# OPR_Main_v2.net
KiCad netlist of a schematic drawn in EAGLE
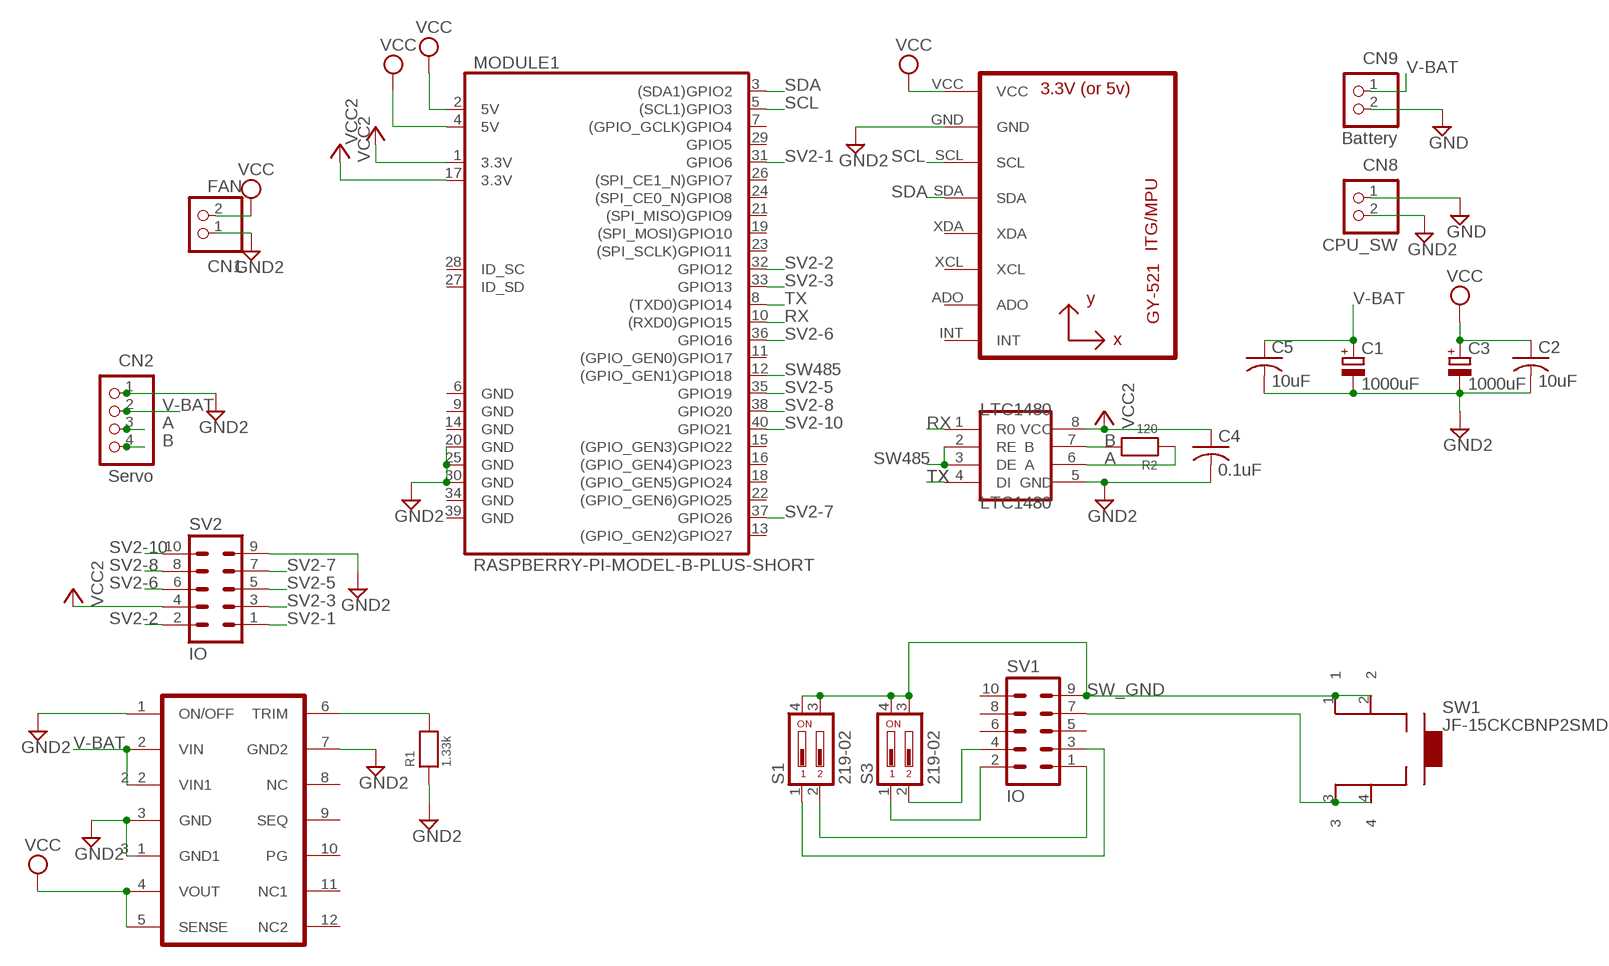
[diagram p0: schematic, sheet 1]

(export (version "E")
  (design (tool "Eeschema 10.0.6"))
  (components
    (comp (ref "C1")
      (value "1000uF")
      (footprint "eagle-import:E5-10,5")
      (libsource (lib "eagle-import") (part "CPOL-EUE5-10.5"))
    )
    (comp (ref "C2")
      (value "10uF")
      (footprint "eagle-import:C3225")
      (libsource (lib "eagle-import") (part "C-USC3225"))
    )
    (comp (ref "C3")
      (value "1000uF")
      (footprint "eagle-import:E5-10,5")
      (libsource (lib "eagle-import") (part "CPOL-EUE5-10.5"))
    )
    (comp (ref "C4")
      (value "0.1uF")
      (footprint "eagle-import:C2012")
      (libsource (lib "eagle-import") (part "rcl_C-USC2012"))
    )
    (comp (ref "C5")
      (value "10uF")
      (footprint "eagle-import:C3225")
      (libsource (lib "eagle-import") (part "C-USC3225"))
    )
    (comp (ref "CN1")
      (value "FAN")
      (footprint "eagle-import:B2B-XH-A")
      (libsource (lib "eagle-import") (part "B2B-XH-A"))
    )
    (comp (ref "CN2")
      (value "Servo")
      (footprint "eagle-import:S4B-XH-A")
      (libsource (lib "eagle-import") (part "S4B-XH-A"))
    )
    (comp (ref "CN8")
      (value "CPU_SW")
      (footprint "eagle-import:B2P-VH")
      (libsource (lib "eagle-import") (part "B2P-VH"))
    )
    (comp (ref "CN9")
      (value "Battery")
      (footprint "eagle-import:B2P-VH")
      (libsource (lib "eagle-import") (part "B2P-VH"))
    )
    (comp (ref "LTC1480")
      (value "LTC1480")
      (footprint "eagle-import:SOIC-8")
      (libsource (lib "eagle-import") (part "LTC1480"))
    )
    (comp (ref "MODULE1")
      (value "RASPBERRY-PI-MODEL-B-PLUS-SHORT")
      (footprint "eagle-import:RASPBERRY-PI-MODEL-B-PLUS-SHORT")
      (libsource (lib "eagle-import") (part "RASPBERRY-PI-MODEL-B-PLUS-SHORT"))
    )
    (comp (ref "R1")
      (value "1.33k")
      (footprint "eagle-import:0805_NOTHERMALS")
      (libsource (lib "eagle-import") (part "RESISTOR0805_NOTHERMALS"))
    )
    (comp (ref "R2")
      (value "120")
      (footprint "eagle-import:0805_NOTHERMALS")
      (libsource (lib "eagle-import") (part "RESISTOR0805_NOTHERMALS"))
    )
    (comp (ref "S1")
      (value "219-02")
      (footprint "eagle-import:CTS-219-02")
      (libsource (lib "eagle-import") (part "219-02"))
    )
    (comp (ref "S3")
      (value "219-02")
      (footprint "eagle-import:CTS-219-02")
      (libsource (lib "eagle-import") (part "219-02"))
    )
    (comp (ref "SV1")
      (value "IO")
      (footprint "eagle-import:ML10")
      (libsource (lib "eagle-import") (part "ML10"))
    )
    (comp (ref "SV2")
      (value "IO")
      (footprint "eagle-import:ML10")
      (libsource (lib "eagle-import") (part "ML10"))
    )
    (comp (ref "SW1")
      (value "JF-15CKCBNP2SMD")
      (footprint "eagle-import:JF-15CKCBNP2-SMD")
      (libsource (lib "eagle-import") (part "JF-15CKCBNP2SMD"))
    )
    (comp (ref "U$3")
      (value "OKL-T/W-12N-C")
      (footprint "eagle-import:OKL_T6_W12")
      (libsource (lib "eagle-import") (part "OKL_T6_W12"))
    )
    (comp (ref "U1")
      (value "GY-521MPU6050")
      (footprint "eagle-import:GY-521")
      (libsource (lib "eagle-import") (part "GY-521MPU6050"))
    )
  )
  (nets
    (net (code "1") (name "/A") (class "Default")
      (node (ref "CN2") (pin "3") (pinfunction "3_3") (pintype "passive"))
      (node (ref "LTC1480") (pin "6") (pinfunction "A_6") (pintype "bidirectional"))
      (node (ref "R2") (pin "1") (pinfunction "1_1") (pintype "passive"))
    )
    (net (code "2") (name "/B") (class "Default")
      (node (ref "CN2") (pin "4") (pinfunction "4_4") (pintype "passive"))
      (node (ref "LTC1480") (pin "7") (pinfunction "B_7") (pintype "passive"))
      (node (ref "R2") (pin "2") (pinfunction "2_2") (pintype "passive"))
    )
    (net (code "3") (name "/RX") (class "Default")
      (node (ref "LTC1480") (pin "1") (pinfunction "R0_1") (pintype "passive"))
      (node (ref "MODULE1") (pin "10") (pinfunction "(RXD0)GPIO15_10") (pintype "passive"))
    )
    (net (code "4") (name "/SCL") (class "Default")
      (node (ref "MODULE1") (pin "5") (pinfunction "(SCL1)GPIO3_5") (pintype "passive"))
      (node (ref "U1") (pin "SCL") (pinfunction "SCL_SCL") (pintype "bidirectional"))
    )
    (net (code "5") (name "/SDA") (class "Default")
      (node (ref "MODULE1") (pin "3") (pinfunction "(SDA1)GPIO2_3") (pintype "passive"))
      (node (ref "U1") (pin "SDA") (pinfunction "SDA_SDA") (pintype "bidirectional"))
    )
    (net (code "6") (name "/SV2-1") (class "Default")
      (node (ref "MODULE1") (pin "31") (pinfunction "GPIO6_31") (pintype "passive"))
      (node (ref "SV2") (pin "1") (pinfunction "1_1") (pintype "passive"))
    )
    (net (code "7") (name "/SV2-2") (class "Default")
      (node (ref "MODULE1") (pin "32") (pinfunction "GPIO12_32") (pintype "passive"))
      (node (ref "SV2") (pin "2") (pinfunction "2_2") (pintype "passive"))
    )
    (net (code "8") (name "/SV2-3") (class "Default")
      (node (ref "MODULE1") (pin "33") (pinfunction "GPIO13_33") (pintype "passive"))
      (node (ref "SV2") (pin "3") (pinfunction "3_3") (pintype "passive"))
    )
    (net (code "9") (name "/SV2-5") (class "Default")
      (node (ref "MODULE1") (pin "35") (pinfunction "GPIO19_35") (pintype "passive"))
      (node (ref "SV2") (pin "5") (pinfunction "5_5") (pintype "passive"))
    )
    (net (code "10") (name "/SV2-6") (class "Default")
      (node (ref "MODULE1") (pin "36") (pinfunction "GPIO16_36") (pintype "passive"))
      (node (ref "SV2") (pin "6") (pinfunction "6_6") (pintype "passive"))
    )
    (net (code "11") (name "/SV2-7") (class "Default")
      (node (ref "MODULE1") (pin "37") (pinfunction "GPIO26_37") (pintype "passive"))
      (node (ref "SV2") (pin "7") (pinfunction "7_7") (pintype "passive"))
    )
    (net (code "12") (name "/SV2-8") (class "Default")
      (node (ref "MODULE1") (pin "38") (pinfunction "GPIO20_38") (pintype "passive"))
      (node (ref "SV2") (pin "8") (pinfunction "8_8") (pintype "passive"))
    )
    (net (code "13") (name "/SV2-10") (class "Default")
      (node (ref "MODULE1") (pin "40") (pinfunction "GPIO21_40") (pintype "passive"))
      (node (ref "SV2") (pin "10") (pinfunction "10_10") (pintype "passive"))
    )
    (net (code "14") (name "/SW485") (class "Default")
      (node (ref "LTC1480") (pin "2") (pinfunction "RE_2") (pintype "passive"))
      (node (ref "LTC1480") (pin "3") (pinfunction "DE_3") (pintype "passive"))
      (node (ref "MODULE1") (pin "12") (pinfunction "(GPIO_GEN1)GPIO18_12") (pintype "passive"))
    )
    (net (code "15") (name "/SW_GND") (class "Default")
      (node (ref "S1") (pin "3") (pinfunction "3_3") (pintype "passive"))
      (node (ref "S1") (pin "4") (pinfunction "4_4") (pintype "passive"))
      (node (ref "S3") (pin "3") (pinfunction "3_3") (pintype "passive"))
      (node (ref "S3") (pin "4") (pinfunction "4_4") (pintype "passive"))
      (node (ref "SV1") (pin "9") (pinfunction "9_9") (pintype "passive"))
      (node (ref "SW1") (pin "1") (pinfunction "1_1") (pintype "bidirectional"))
      (node (ref "SW1") (pin "2") (pinfunction "2_2") (pintype "bidirectional"))
    )
    (net (code "16") (name "/TX") (class "Default")
      (node (ref "LTC1480") (pin "4") (pinfunction "DI_4") (pintype "passive"))
      (node (ref "MODULE1") (pin "8") (pinfunction "(TXD0)GPIO14_8") (pintype "passive"))
    )
    (net (code "17") (name "/V-BAT") (class "Default")
      (node (ref "C1") (pin "+") (pinfunction "+_+") (pintype "passive"))
      (node (ref "C5") (pin "1") (pinfunction "1_1") (pintype "passive"))
      (node (ref "CN2") (pin "2") (pinfunction "2_2") (pintype "passive"))
      (node (ref "CN9") (pin "1") (pinfunction "1_1") (pintype "passive"))
      (node (ref "U$3") (pin "2") (pinfunction "VIN_2") (pintype "bidirectional"))
      (node (ref "U$3") (pin "2_2") (pinfunction "VIN1_2_2") (pintype "bidirectional"))
    )
    (net (code "18") (name "GND") (class "Default")
      (node (ref "CN8") (pin "1") (pinfunction "1_1") (pintype "passive"))
      (node (ref "CN9") (pin "2") (pinfunction "2_2") (pintype "passive"))
    )
    (net (code "19") (name "GND2") (class "Default")
      (node (ref "C1") (pin "-") (pinfunction "-_-") (pintype "passive"))
      (node (ref "C2") (pin "2") (pinfunction "2_2") (pintype "passive"))
      (node (ref "C3") (pin "-") (pinfunction "-_-") (pintype "passive"))
      (node (ref "C4") (pin "2") (pinfunction "2_2") (pintype "passive"))
      (node (ref "C5") (pin "2") (pinfunction "2_2") (pintype "passive"))
      (node (ref "CN1") (pin "1") (pinfunction "1_1") (pintype "passive"))
      (node (ref "CN2") (pin "1") (pinfunction "1_1") (pintype "passive"))
      (node (ref "CN8") (pin "2") (pinfunction "2_2") (pintype "passive"))
      (node (ref "LTC1480") (pin "5") (pinfunction "GND_5") (pintype "passive"))
      (node (ref "MODULE1") (pin "20") (pinfunction "GND_20") (pintype "passive"))
      (node (ref "MODULE1") (pin "25") (pinfunction "GND_25") (pintype "passive"))
      (node (ref "MODULE1") (pin "30") (pinfunction "GND_30") (pintype "passive"))
      (node (ref "R1") (pin "1") (pinfunction "1_1") (pintype "passive"))
      (node (ref "SV2") (pin "9") (pinfunction "9_9") (pintype "passive"))
      (node (ref "U$3") (pin "1") (pinfunction "ON/OFF_1") (pintype "bidirectional"))
      (node (ref "U$3") (pin "3") (pinfunction "GND_3") (pintype "bidirectional"))
      (node (ref "U$3") (pin "3_1") (pinfunction "GND1_3_1") (pintype "bidirectional"))
      (node (ref "U$3") (pin "7") (pinfunction "GND2_7") (pintype "bidirectional"))
      (node (ref "U1") (pin "GND") (pinfunction "GND_GND") (pintype "bidirectional"))
    )
    (net (code "20") (name "Net-(S1-Pad1)") (class "Default")
      (node (ref "S1") (pin "1") (pinfunction "1_1") (pintype "passive"))
      (node (ref "SV1") (pin "3") (pinfunction "3_3") (pintype "passive"))
    )
    (net (code "21") (name "Net-(S1-Pad2)") (class "Default")
      (node (ref "S1") (pin "2") (pinfunction "2_2") (pintype "passive"))
      (node (ref "SV1") (pin "1") (pinfunction "1_1") (pintype "passive"))
    )
    (net (code "22") (name "Net-(S3-Pad1)") (class "Default")
      (node (ref "S3") (pin "1") (pinfunction "1_1") (pintype "passive"))
      (node (ref "SV1") (pin "2") (pinfunction "2_2") (pintype "passive"))
    )
    (net (code "23") (name "Net-(S3-Pad2)") (class "Default")
      (node (ref "S3") (pin "2") (pinfunction "2_2") (pintype "passive"))
      (node (ref "SV1") (pin "4") (pinfunction "4_4") (pintype "passive"))
    )
    (net (code "24") (name "Net-(SV1-Pad7)") (class "Default")
      (node (ref "SV1") (pin "7") (pinfunction "7_7") (pintype "passive"))
      (node (ref "SW1") (pin "3") (pinfunction "3_3") (pintype "bidirectional"))
      (node (ref "SW1") (pin "4") (pinfunction "4_4") (pintype "bidirectional"))
    )
    (net (code "25") (name "Net-(U$3-TRIM)") (class "Default")
      (node (ref "R1") (pin "2") (pinfunction "2_2") (pintype "passive"))
      (node (ref "U$3") (pin "6") (pinfunction "TRIM_6") (pintype "bidirectional"))
    )
    (net (code "26") (name "VCC") (class "Default")
      (node (ref "C2") (pin "1") (pinfunction "1_1") (pintype "passive"))
      (node (ref "C3") (pin "+") (pinfunction "+_+") (pintype "passive"))
      (node (ref "CN1") (pin "2") (pinfunction "2_2") (pintype "passive"))
      (node (ref "MODULE1") (pin "2") (pinfunction "5V_2") (pintype "passive"))
      (node (ref "MODULE1") (pin "4") (pinfunction "5V_4") (pintype "passive"))
      (node (ref "U$3") (pin "4") (pinfunction "VOUT_4") (pintype "bidirectional"))
      (node (ref "U$3") (pin "5") (pinfunction "SENSE_5") (pintype "bidirectional"))
      (node (ref "U1") (pin "VCC") (pinfunction "VCC_VCC") (pintype "bidirectional"))
    )
    (net (code "27") (name "VCC2") (class "Default")
      (node (ref "C4") (pin "1") (pinfunction "1_1") (pintype "passive"))
      (node (ref "LTC1480") (pin "8") (pinfunction "VCC_8") (pintype "passive"))
      (node (ref "MODULE1") (pin "1") (pinfunction "3.3V_1") (pintype "passive"))
      (node (ref "MODULE1") (pin "17") (pinfunction "3.3V_17") (pintype "passive"))
      (node (ref "SV2") (pin "4") (pinfunction "4_4") (pintype "passive"))
    )
    (net (code "28") (name "unconnected-(MODULE1-(GPIO_GCLK)GPIO4-Pad7)") (class "Default")
      (node (ref "MODULE1") (pin "7") (pinfunction "(GPIO_GCLK)GPIO4_7") (pintype "passive"))
    )
    (net (code "29") (name "unconnected-(MODULE1-(GPIO_GEN0)GPIO17-Pad11)") (class "Default")
      (node (ref "MODULE1") (pin "11") (pinfunction "(GPIO_GEN0)GPIO17_11") (pintype "passive"))
    )
    (net (code "30") (name "unconnected-(MODULE1-(GPIO_GEN2)GPIO27-Pad13)") (class "Default")
      (node (ref "MODULE1") (pin "13") (pinfunction "(GPIO_GEN2)GPIO27_13") (pintype "passive"))
    )
    (net (code "31") (name "unconnected-(MODULE1-(GPIO_GEN3)GPIO22-Pad15)") (class "Default")
      (node (ref "MODULE1") (pin "15") (pinfunction "(GPIO_GEN3)GPIO22_15") (pintype "passive"))
    )
    (net (code "32") (name "unconnected-(MODULE1-(GPIO_GEN4)GPIO23-Pad16)") (class "Default")
      (node (ref "MODULE1") (pin "16") (pinfunction "(GPIO_GEN4)GPIO23_16") (pintype "passive"))
    )
    (net (code "33") (name "unconnected-(MODULE1-(GPIO_GEN5)GPIO24-Pad18)") (class "Default")
      (node (ref "MODULE1") (pin "18") (pinfunction "(GPIO_GEN5)GPIO24_18") (pintype "passive"))
    )
    (net (code "34") (name "unconnected-(MODULE1-(GPIO_GEN6)GPIO25-Pad22)") (class "Default")
      (node (ref "MODULE1") (pin "22") (pinfunction "(GPIO_GEN6)GPIO25_22") (pintype "passive"))
    )
    (net (code "35") (name "unconnected-(MODULE1-(SPI_CE0_N)GPIO8-Pad24)") (class "Default")
      (node (ref "MODULE1") (pin "24") (pinfunction "(SPI_CE0_N)GPIO8_24") (pintype "passive"))
    )
    (net (code "36") (name "unconnected-(MODULE1-(SPI_CE1_N)GPIO7-Pad26)") (class "Default")
      (node (ref "MODULE1") (pin "26") (pinfunction "(SPI_CE1_N)GPIO7_26") (pintype "passive"))
    )
    (net (code "37") (name "unconnected-(MODULE1-(SPI_MISO)GPIO9-Pad21)") (class "Default")
      (node (ref "MODULE1") (pin "21") (pinfunction "(SPI_MISO)GPIO9_21") (pintype "passive"))
    )
    (net (code "38") (name "unconnected-(MODULE1-(SPI_MOSI)GPIO10-Pad19)") (class "Default")
      (node (ref "MODULE1") (pin "19") (pinfunction "(SPI_MOSI)GPIO10_19") (pintype "passive"))
    )
    (net (code "39") (name "unconnected-(MODULE1-(SPI_SCLK)GPIO11-Pad23)") (class "Default")
      (node (ref "MODULE1") (pin "23") (pinfunction "(SPI_SCLK)GPIO11_23") (pintype "passive"))
    )
    (net (code "40") (name "unconnected-(MODULE1-GND-Pad6)") (class "Default")
      (node (ref "MODULE1") (pin "6") (pinfunction "GND_6") (pintype "passive"))
    )
    (net (code "41") (name "unconnected-(MODULE1-GND-Pad9)") (class "Default")
      (node (ref "MODULE1") (pin "9") (pinfunction "GND_9") (pintype "passive"))
    )
    (net (code "42") (name "unconnected-(MODULE1-GND-Pad14)") (class "Default")
      (node (ref "MODULE1") (pin "14") (pinfunction "GND_14") (pintype "passive"))
    )
    (net (code "43") (name "unconnected-(MODULE1-GND-Pad34)") (class "Default")
      (node (ref "MODULE1") (pin "34") (pinfunction "GND_34") (pintype "passive"))
    )
    (net (code "44") (name "unconnected-(MODULE1-GND-Pad39)") (class "Default")
      (node (ref "MODULE1") (pin "39") (pinfunction "GND_39") (pintype "passive"))
    )
    (net (code "45") (name "unconnected-(MODULE1-GPIO5-Pad29)") (class "Default")
      (node (ref "MODULE1") (pin "29") (pinfunction "GPIO5_29") (pintype "passive"))
    )
    (net (code "46") (name "unconnected-(MODULE1-ID_SC-Pad28)") (class "Default")
      (node (ref "MODULE1") (pin "28") (pinfunction "ID_SC_28") (pintype "passive"))
    )
    (net (code "47") (name "unconnected-(MODULE1-ID_SD-Pad27)") (class "Default")
      (node (ref "MODULE1") (pin "27") (pinfunction "ID_SD_27") (pintype "passive"))
    )
    (net (code "48") (name "unconnected-(SV1-Pad5)") (class "Default")
      (node (ref "SV1") (pin "5") (pinfunction "5_5") (pintype "passive"))
    )
    (net (code "49") (name "unconnected-(SV1-Pad6)") (class "Default")
      (node (ref "SV1") (pin "6") (pinfunction "6_6") (pintype "passive"))
    )
    (net (code "50") (name "unconnected-(SV1-Pad8)") (class "Default")
      (node (ref "SV1") (pin "8") (pinfunction "8_8") (pintype "passive"))
    )
    (net (code "51") (name "unconnected-(SV1-Pad10)") (class "Default")
      (node (ref "SV1") (pin "10") (pinfunction "10_10") (pintype "passive"))
    )
    (net (code "52") (name "unconnected-(U$3-NC-Pad8)") (class "Default")
      (node (ref "U$3") (pin "8") (pinfunction "NC_8") (pintype "bidirectional"))
    )
    (net (code "53") (name "unconnected-(U$3-NC1-Pad11)") (class "Default")
      (node (ref "U$3") (pin "11") (pinfunction "NC1_11") (pintype "bidirectional"))
    )
    (net (code "54") (name "unconnected-(U$3-NC2-Pad12)") (class "Default")
      (node (ref "U$3") (pin "12") (pinfunction "NC2_12") (pintype "bidirectional"))
    )
    (net (code "55") (name "unconnected-(U$3-PG-Pad10)") (class "Default")
      (node (ref "U$3") (pin "10") (pinfunction "PG_10") (pintype "bidirectional"))
    )
    (net (code "56") (name "unconnected-(U$3-SEQ-Pad9)") (class "Default")
      (node (ref "U$3") (pin "9") (pinfunction "SEQ_9") (pintype "bidirectional"))
    )
    (net (code "57") (name "unconnected-(U1-PadADO)") (class "Default")
      (node (ref "U1") (pin "ADO") (pinfunction "ADO_ADO") (pintype "bidirectional"))
    )
    (net (code "58") (name "unconnected-(U1-PadINT)") (class "Default")
      (node (ref "U1") (pin "INT") (pinfunction "INT_INT") (pintype "bidirectional"))
    )
    (net (code "59") (name "unconnected-(U1-PadXCL)") (class "Default")
      (node (ref "U1") (pin "XCL") (pinfunction "XCL_XCL") (pintype "bidirectional"))
    )
    (net (code "60") (name "unconnected-(U1-PadXDA)") (class "Default")
      (node (ref "U1") (pin "XDA") (pinfunction "XDA_XDA") (pintype "bidirectional"))
    )
  )
)
